# LoadCell.net
KiCad netlist of a schematic drawn in Altium Designer
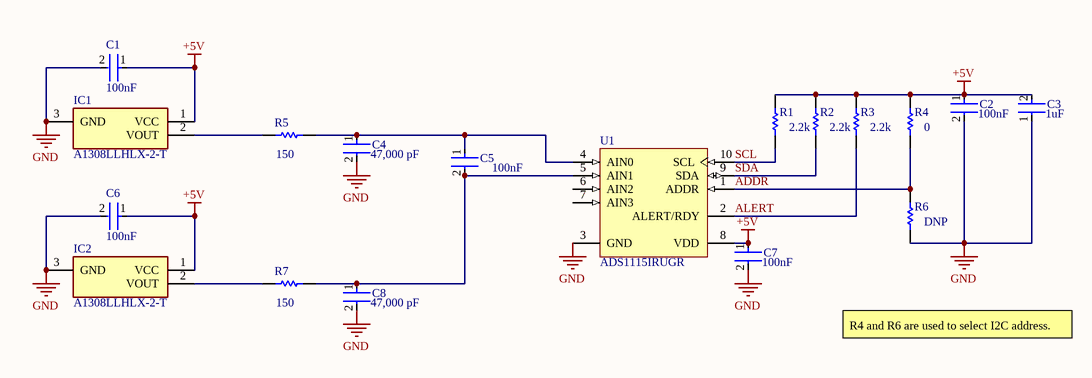
[diagram p0: LoadCell.SchDoc]

(export (version "E")
  (design (tool "Eeschema 10.0.6"))
  (components
    (comp (ref "C1")
      (value "CGA3E2X7R1H104K080AA")
      (footprint "FP-CGA3E-0_3-0_1-IPC_A")
      (description "Cap Ceramic 100nF 50V X7R 10% Pad SMD 0603 +125°C Automotive T/R")
      (fields
        (field (name "TOLERANCE") "10%")
        (field (name "CAPACITANCE") "100nF")
        (field (name "VOLTAGE") "50V")
      )
      (libsource (lib "Altium Content Vault") (part "b4654b650e69147ec39a6b967a45e02"))
    )
    (comp (ref "C2")
      (value "CGA3E2X7R1H104K080AA")
      (footprint "FP-CGA3E-0_3-0_1-IPC_A")
      (description "Cap Ceramic 100nF 50V X7R 10% Pad SMD 0603 +125°C Automotive T/R")
      (fields
        (field (name "TOLERANCE") "10%")
        (field (name "CAPACITANCE") "100nF")
        (field (name "VOLTAGE") "50V")
      )
      (libsource (lib "Altium Content Vault") (part "b4654b650e69147ec39a6b967a45e02"))
    )
    (comp (ref "C3")
      (value "C1608X5R1H105K080AB")
      (footprint "FP-C1608-080-0_1-IPC_B")
      (description "Multilayer Ceramic Capacitors 1μF ±10% 50V X5R SMD 0603")
      (fields
        (field (name "VOLTAGE") "50V")
        (field (name "CAPACITANCE") "1uF")
        (field (name "TOLERANCE") "10%")
      )
      (libsource (lib "Altium Content Vault") (part "236180d848d6139a670b325ea6854c9"))
    )
    (comp (ref "C4")
      (value "47,000 pF")
      (footprint "FP-C0603C-CF-MFG")
      (description "CAP CER 0.047UF 50V 10% X7R 0603")
      (fields (field (name "TOLERANCE") "0.1") (field (name "MANUFACTURER") "KEMET"))
      (libsource (lib "Altium Content Vault") (part "b4654b650e69147ec39a6b967a45e02"))
    )
    (comp (ref "C5")
      (value "CGA3E2X7R1H104K080AA")
      (footprint "FP-CGA3E-0_3-0_1-IPC_A")
      (description "Cap Ceramic 100nF 50V X7R 10% Pad SMD 0603 +125°C Automotive T/R")
      (fields
        (field (name "TOLERANCE") "10%")
        (field (name "CAPACITANCE") "100nF")
        (field (name "VOLTAGE") "50V")
      )
      (libsource (lib "Altium Content Vault") (part "b4654b650e69147ec39a6b967a45e02"))
    )
    (comp (ref "C6")
      (value "CGA3E2X7R1H104K080AA")
      (footprint "FP-CGA3E-0_3-0_1-IPC_A")
      (description "Cap Ceramic 100nF 50V X7R 10% Pad SMD 0603 +125°C Automotive T/R")
      (fields
        (field (name "TOLERANCE") "10%")
        (field (name "CAPACITANCE") "100nF")
        (field (name "VOLTAGE") "50V")
      )
      (libsource (lib "Altium Content Vault") (part "b4654b650e69147ec39a6b967a45e02"))
    )
    (comp (ref "C7")
      (value "CGA3E2X7R1H104K080AA")
      (footprint "FP-CGA3E-0_3-0_1-IPC_A")
      (description "Cap Ceramic 100nF 50V X7R 10% Pad SMD 0603 +125°C Automotive T/R")
      (fields
        (field (name "TOLERANCE") "10%")
        (field (name "CAPACITANCE") "100nF")
        (field (name "VOLTAGE") "50V")
      )
      (libsource (lib "Altium Content Vault") (part "b4654b650e69147ec39a6b967a45e02"))
    )
    (comp (ref "C8")
      (value "47,000 pF")
      (footprint "FP-C0603C-CF-MFG")
      (description "CAP CER 0.047UF 50V 10% X7R 0603")
      (fields (field (name "TOLERANCE") "0.1") (field (name "MANUFACTURER") "KEMET"))
      (libsource (lib "Altium Content Vault") (part "b4654b650e69147ec39a6b967a45e02"))
    )
    (comp (ref "IC1")
      (value "A1308LLHLX-2-T")
      (footprint "SamacSys:SOT95P285X113-3N")
      (description "Integrated Circuit")
      (fields (field (name "MOUSER PART NUMBER") "250-A1308LLHLX-2-T"))
      (libsource (lib "*") (part "A1308LLHLX-2-T"))
    )
    (comp (ref "IC2")
      (value "A1308LLHLX-2-T")
      (footprint "SamacSys:SOT95P285X113-3N")
      (description "Integrated Circuit")
      (fields (field (name "MOUSER PART NUMBER") "250-A1308LLHLX-2-T"))
      (libsource (lib "*") (part "A1308LLHLX-2-T"))
    )
    (comp (ref "R1")
      (value "2.2k")
      (footprint "RESC1609X50X30NL10T20")
      (fields (field (name "PART NUMBER") "CRCW06032K20FKEA") (field (name "MANUFACTURER") "Vishay Dale"))
      (libsource (lib "Altium Content Vault") (part "RES"))
    )
    (comp (ref "R2")
      (value "2.2k")
      (footprint "RESC1609X50X30NL10T20")
      (fields (field (name "PART NUMBER") "CRCW06032K20FKEA") (field (name "MANUFACTURER") "Vishay Dale"))
      (libsource (lib "Altium Content Vault") (part "RES"))
    )
    (comp (ref "R3")
      (value "2.2k")
      (footprint "RESC1609X50X30NL10T20")
      (fields (field (name "PART NUMBER") "CRCW06032K20FKEA") (field (name "MANUFACTURER") "Vishay Dale"))
      (libsource (lib "Altium Content Vault") (part "RES"))
    )
    (comp (ref "R4")
      (value "RC0603JR-070RL")
      (footprint "RESC1608X55X25ML10T15")
      (description "Chip Resistor, 0 Ohm, +/- 5%, 0.1 W, -55 to 155 degC, 0603 (1608 Metric), RoHS, Tape and Reel")
      (fields
        (field (name "TOLERANCE") "5%")
        (field (name "RESISTANCE") "0")
        (field (name "MANUFACTURER") "Yageo")
      )
      (libsource (lib "Altium Content Vault") (part "RES-2"))
    )
    (comp (ref "R5")
      (value "150")
      (footprint "RESC1608X55X25ML10T15")
      (description "Chip Resistor, 150 Ohm, +/- 1%, 0.1 W, -55 to 155 degC, 0603 (1608 Metric), RoHS, Tape and Reel")
      (fields (field (name "Comment") "RC0603FR-07150RL"))
      (libsource (lib "Altium Content Vault") (part "RES-2"))
    )
    (comp (ref "R6")
      (value "RC0603JR-070RL")
      (footprint "RESC1608X55X25ML10T15")
      (description "Chip Resistor, 0 Ohm, +/- 5%, 0.1 W, -55 to 155 degC, 0603 (1608 Metric), RoHS, Tape and Reel")
      (fields
        (field (name "TOLERANCE") "5%")
        (field (name "RESISTANCE") "DNP")
        (field (name "MANUFACTURER") "Yageo")
      )
      (libsource (lib "Altium Content Vault") (part "RES-2"))
    )
    (comp (ref "R7")
      (value "150")
      (footprint "RESC1608X55X25ML10T15")
      (description "Chip Resistor, 150 Ohm, +/- 1%, 0.1 W, -55 to 155 degC, 0603 (1608 Metric), RoHS, Tape and Reel")
      (fields (field (name "Comment") "RC0603FR-07150RL"))
      (libsource (lib "Altium Content Vault") (part "RES-2"))
    )
    (comp (ref "U1")
      (value "ADS1115IRUGR")
      (footprint "TI-RUG10_V")
      (fields (field (name "MANUFACTURER") "Texas Instruments"))
      (libsource (lib "Altium Content Vault") (part "TI-ADS1015_1115-10"))
    )
  )
  (nets
    (net (code "1") (name "+5V") (class "Default")
      (node (ref "C1") (pin "1") (pinfunction "1_1") (pintype "passive"))
      (node (ref "C2") (pin "1") (pinfunction "1_1") (pintype "passive"))
      (node (ref "C3") (pin "2") (pinfunction "2_2") (pintype "passive"))
      (node (ref "C6") (pin "1") (pinfunction "1_1") (pintype "passive"))
      (node (ref "C7") (pin "1") (pinfunction "1_1") (pintype "passive"))
      (node (ref "IC1") (pin "1") (pinfunction "VCC_1") (pintype "passive"))
      (node (ref "IC2") (pin "1") (pinfunction "VCC_1") (pintype "passive"))
      (node (ref "R1") (pin "2") (pinfunction "2_2") (pintype "passive"))
      (node (ref "R2") (pin "2") (pinfunction "2_2") (pintype "passive"))
      (node (ref "R3") (pin "2") (pinfunction "2_2") (pintype "passive"))
      (node (ref "R4") (pin "2") (pinfunction "2_2") (pintype "passive"))
      (node (ref "U1") (pin "8") (pinfunction "VDD_8") (pintype "power_in"))
    )
    (net (code "2") (name "/ADDR") (class "Default")
      (node (ref "R4") (pin "1") (pinfunction "1_1") (pintype "passive"))
      (node (ref "R6") (pin "2") (pinfunction "2_2") (pintype "passive"))
      (node (ref "U1") (pin "1") (pinfunction "ADDR_1") (pintype "input"))
    )
    (net (code "3") (name "/ALERT") (class "Default")
      (node (ref "R3") (pin "1") (pinfunction "1_1") (pintype "passive"))
      (node (ref "U1") (pin "2") (pinfunction "ALERT/RDY_2") (pintype "open_collector"))
    )
    (net (code "4") (name "/SCL") (class "Default")
      (node (ref "R1") (pin "1") (pinfunction "1_1") (pintype "passive"))
      (node (ref "U1") (pin "10") (pinfunction "SCL_10") (pintype "input"))
    )
    (net (code "5") (name "/SDA") (class "Default")
      (node (ref "R2") (pin "1") (pinfunction "1_1") (pintype "passive"))
      (node (ref "U1") (pin "9") (pinfunction "SDA_9") (pintype "bidirectional"))
    )
    (net (code "6") (name "GND") (class "Default")
      (node (ref "C1") (pin "2") (pinfunction "2_2") (pintype "passive"))
      (node (ref "C2") (pin "2") (pinfunction "2_2") (pintype "passive"))
      (node (ref "C3") (pin "1") (pinfunction "1_1") (pintype "passive"))
      (node (ref "C4") (pin "2") (pinfunction "2_2") (pintype "passive"))
      (node (ref "C6") (pin "2") (pinfunction "2_2") (pintype "passive"))
      (node (ref "C7") (pin "2") (pinfunction "2_2") (pintype "passive"))
      (node (ref "C8") (pin "2") (pinfunction "2_2") (pintype "passive"))
      (node (ref "IC1") (pin "3") (pinfunction "GND_3") (pintype "passive"))
      (node (ref "IC2") (pin "3") (pinfunction "GND_3") (pintype "passive"))
      (node (ref "R6") (pin "1") (pinfunction "1_1") (pintype "passive"))
      (node (ref "U1") (pin "3") (pinfunction "GND_3") (pintype "power_in"))
    )
    (net (code "7") (name "Net-(IC1-VOUT)") (class "Default")
      (node (ref "IC1") (pin "2") (pinfunction "VOUT_2") (pintype "passive"))
      (node (ref "R5") (pin "1") (pinfunction "1_1") (pintype "passive"))
    )
    (net (code "8") (name "Net-(IC2-VOUT)") (class "Default")
      (node (ref "IC2") (pin "2") (pinfunction "VOUT_2") (pintype "passive"))
      (node (ref "R7") (pin "1") (pinfunction "1_1") (pintype "passive"))
    )
    (net (code "9") (name "Net-(U1-AIN0)") (class "Default")
      (node (ref "C4") (pin "1") (pinfunction "1_1") (pintype "passive"))
      (node (ref "C5") (pin "1") (pinfunction "1_1") (pintype "passive"))
      (node (ref "R5") (pin "2") (pinfunction "2_2") (pintype "passive"))
      (node (ref "U1") (pin "4") (pinfunction "AIN0_4") (pintype "input"))
    )
    (net (code "10") (name "Net-(U1-AIN1)") (class "Default")
      (node (ref "C5") (pin "2") (pinfunction "2_2") (pintype "passive"))
      (node (ref "C8") (pin "1") (pinfunction "1_1") (pintype "passive"))
      (node (ref "R7") (pin "2") (pinfunction "2_2") (pintype "passive"))
      (node (ref "U1") (pin "5") (pinfunction "AIN1_5") (pintype "input"))
    )
    (net (code "11") (name "unconnected-(U1-AIN2-Pad6)") (class "Default")
      (node (ref "U1") (pin "6") (pinfunction "AIN2_6") (pintype "input"))
    )
    (net (code "12") (name "unconnected-(U1-AIN3-Pad7)") (class "Default")
      (node (ref "U1") (pin "7") (pinfunction "AIN3_7") (pintype "input"))
    )
  )
)
